# MicroUSB_SMD.net
KiCad netlist of a schematic drawn in EAGLE
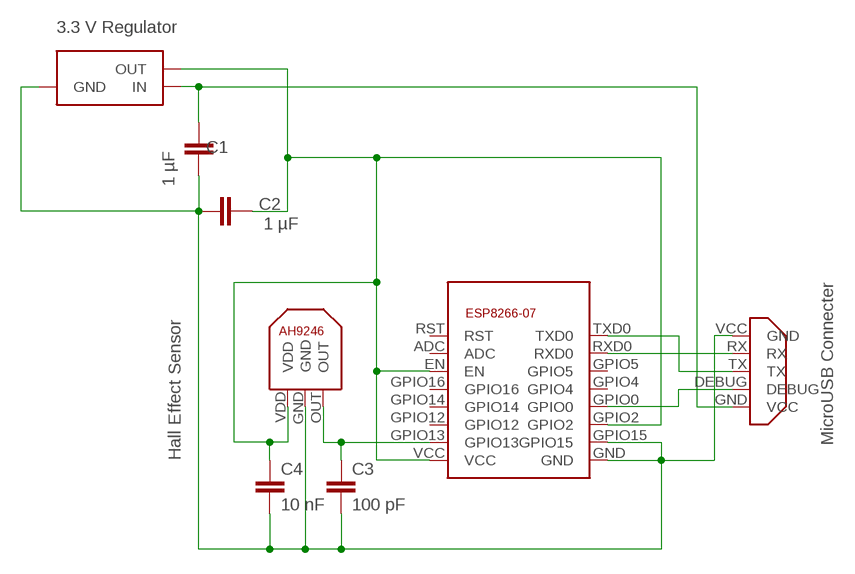
[diagram p0: schematic, sheet 1]

(export (version "E")
  (design (tool "Eeschema 10.0.6"))
  (components
    (comp (ref "C1")
      (value "1 µF")
      (footprint "eagle-import:0805")
      (libsource (lib "eagle-import") (part "0.33UF/330NF-0805-50V-10%"))
    )
    (comp (ref "C2")
      (value "1 µF")
      (footprint "eagle-import:0805")
      (libsource (lib "eagle-import") (part "0.33UF/330NF-0805-50V-10%"))
    )
    (comp (ref "C3")
      (value "100 pF")
      (footprint "eagle-import:0805")
      (libsource (lib "eagle-import") (part "0.33UF/330NF-0805-50V-10%"))
    )
    (comp (ref "C4")
      (value "10 nF")
      (footprint "eagle-import:0805")
      (libsource (lib "eagle-import") (part "0.33UF/330NF-0805-50V-10%"))
    )
    (comp (ref "U$1")
      (value "ESP8266-07SMD")
      (footprint "eagle-import:ESP8266-07")
      (libsource (lib "eagle-import") (part "ESP8266-07SMD"))
    )
    (comp (ref "U$3")
      (value "AH9246SC59")
      (footprint "eagle-import:SC59")
      (libsource (lib "eagle-import") (part "AH9246SC59"))
    )
    (comp (ref "U$4")
      (value "MICROUSB609-4613-1-ND")
      (footprint "eagle-import:MICROUSB")
      (libsource (lib "eagle-import") (part "MICROUSB609-4613-1-ND"))
    )
    (comp (ref "U$5")
      (value "AZ1117E")
      (footprint "eagle-import:SOT-223")
      (libsource (lib "eagle-import") (part "AZ1117E"))
    )
  )
  (nets
    (net (code "1") (name "Net-(C2-Pad2)") (class "Default")
      (node (ref "C2") (pin "2") (pinfunction "2_2") (pintype "passive"))
      (node (ref "C4") (pin "1") (pinfunction "1_1") (pintype "passive"))
      (node (ref "U$1") (pin "EN") (pinfunction "EN_EN") (pintype "input"))
      (node (ref "U$1") (pin "GPIO2") (pinfunction "GPIO2_GPIO2") (pintype "bidirectional"))
      (node (ref "U$1") (pin "VCC") (pinfunction "VCC_VCC") (pintype "power_in"))
      (node (ref "U$3") (pin "VDD") (pinfunction "VDD_VDD") (pintype "power_in"))
      (node (ref "U$5") (pin "P$1") (pinfunction "OUT_P$1") (pintype "output"))
      (node (ref "U$5") (pin "P$2") (pinfunction "OUT_P$2") (pintype "output"))
    )
    (net (code "2") (name "Net-(C3-Pad1)") (class "Default")
      (node (ref "C3") (pin "1") (pinfunction "1_1") (pintype "passive"))
      (node (ref "U$1") (pin "GPIO13") (pinfunction "GPIO13_GPIO13") (pintype "bidirectional"))
      (node (ref "U$3") (pin "OUT") (pinfunction "OUT_OUT") (pintype "output"))
    )
    (net (code "3") (name "Net-(U$1-PadGPIO0)") (class "Default")
      (node (ref "U$1") (pin "GPIO0") (pinfunction "GPIO0_GPIO0") (pintype "bidirectional"))
      (node (ref "U$4") (pin "DEBUG") (pinfunction "DEBUG_DEBUG") (pintype "bidirectional"))
    )
    (net (code "4") (name "Net-(U$1-PadRXD0)") (class "Default")
      (node (ref "U$1") (pin "RXD0") (pinfunction "RXD0_RXD0") (pintype "bidirectional"))
      (node (ref "U$4") (pin "RX") (pinfunction "RX_RX") (pintype "bidirectional"))
    )
    (net (code "5") (name "Net-(U$1-PadTXD0)") (class "Default")
      (node (ref "U$1") (pin "TXD0") (pinfunction "TXD0_TXD0") (pintype "bidirectional"))
      (node (ref "U$4") (pin "TX") (pinfunction "TX_TX") (pintype "bidirectional"))
    )
    (net (code "6") (name "Net-(U$4-GND)") (class "Default")
      (node (ref "C1") (pin "2") (pinfunction "2_2") (pintype "passive"))
      (node (ref "C2") (pin "1") (pinfunction "1_1") (pintype "passive"))
      (node (ref "C3") (pin "2") (pinfunction "2_2") (pintype "passive"))
      (node (ref "C4") (pin "2") (pinfunction "2_2") (pintype "passive"))
      (node (ref "U$1") (pin "GND") (pinfunction "GND_GND") (pintype "power_in"))
      (node (ref "U$1") (pin "GPIO15") (pinfunction "GPIO15_GPIO15") (pintype "bidirectional"))
      (node (ref "U$3") (pin "GND") (pinfunction "GND_GND") (pintype "power_in"))
      (node (ref "U$4") (pin "VCC") (pinfunction "GND_VCC") (pintype "power_in"))
      (node (ref "U$5") (pin "P$3") (pinfunction "GND_P$3") (pintype "power_in"))
    )
    (net (code "7") (name "Net-(U$4-VCC)") (class "Default")
      (node (ref "C1") (pin "1") (pinfunction "1_1") (pintype "passive"))
      (node (ref "U$4") (pin "GND") (pinfunction "VCC_GND") (pintype "power_in"))
      (node (ref "U$5") (pin "P$4") (pinfunction "IN_P$4") (pintype "input"))
    )
    (net (code "8") (name "unconnected-(U$1-PadADC)") (class "Default")
      (node (ref "U$1") (pin "ADC") (pinfunction "ADC_ADC") (pintype "input"))
    )
    (net (code "9") (name "unconnected-(U$1-PadGPIO4)") (class "Default")
      (node (ref "U$1") (pin "GPIO4") (pinfunction "GPIO4_GPIO4") (pintype "bidirectional"))
    )
    (net (code "10") (name "unconnected-(U$1-PadGPIO5)") (class "Default")
      (node (ref "U$1") (pin "GPIO5") (pinfunction "GPIO5_GPIO5") (pintype "bidirectional"))
    )
    (net (code "11") (name "unconnected-(U$1-PadGPIO12)") (class "Default")
      (node (ref "U$1") (pin "GPIO12") (pinfunction "GPIO12_GPIO12") (pintype "bidirectional"))
    )
    (net (code "12") (name "unconnected-(U$1-PadGPIO14)") (class "Default")
      (node (ref "U$1") (pin "GPIO14") (pinfunction "GPIO14_GPIO14") (pintype "bidirectional"))
    )
    (net (code "13") (name "unconnected-(U$1-PadGPIO16)") (class "Default")
      (node (ref "U$1") (pin "GPIO16") (pinfunction "GPIO16_GPIO16") (pintype "bidirectional"))
    )
    (net (code "14") (name "unconnected-(U$1-PadRST)") (class "Default")
      (node (ref "U$1") (pin "RST") (pinfunction "RST_RST") (pintype "input"))
    )
  )
)
